# CM4_GPIO.net
KiCad netlist of a schematic drawn in Altium Designer
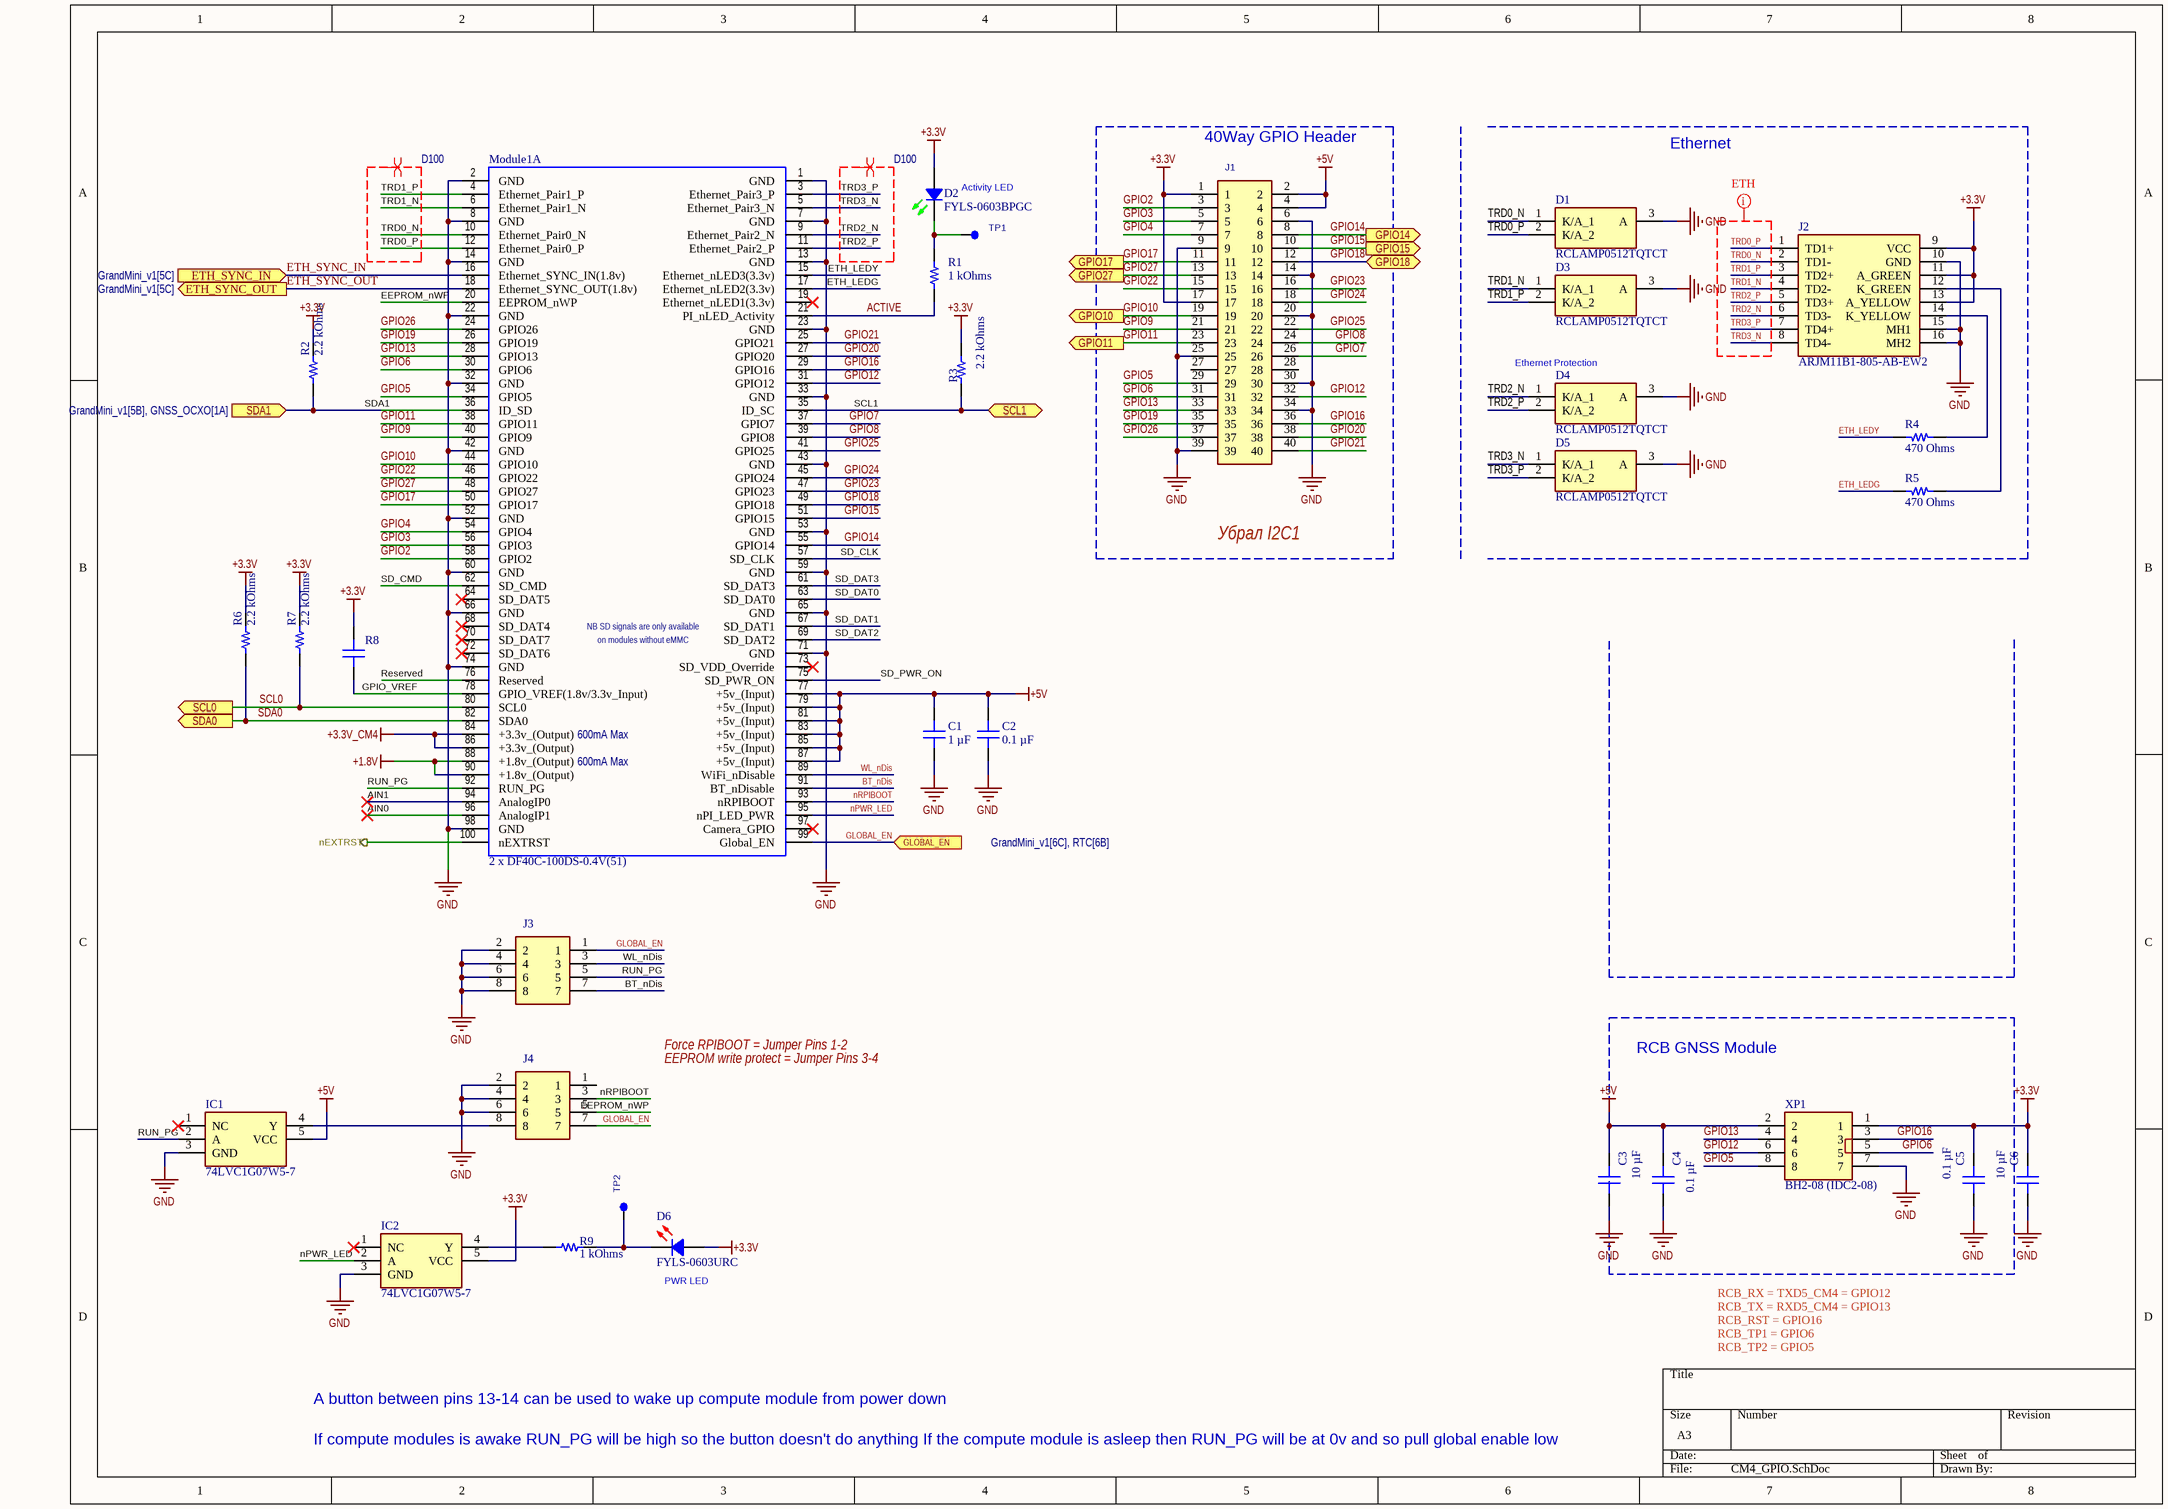
[diagram p0: CM4_GPIO.SchDoc]

(export (version "E")
  (design (tool "Eeschema 10.0.6"))
  (components
    (comp (ref "C1")
      (value "1 µF")
      (footprint "CAP 0603_1608")
      (description "CAP CER 1UF 50V X7R 0603")
      (fields (field (name "PART NUMBER") "CC0603KRX7R9BB105") (field (name "MANUFACTURER") "Yageo"))
      (libsource (lib "Celestial Altium Library - altium_library") (part "Capacitor"))
    )
    (comp (ref "C2")
      (value "0.1 µF")
      (footprint "CAP 0603_1608")
      (description "CAP CER 0.1UF 50V X7R 0603")
      (fields (field (name "PART NUMBER") "CC0603KRX7R9BB104") (field (name "MANUFACTURER") "Yageo"))
      (libsource (lib "Celestial Altium Library - altium_library") (part "Capacitor"))
    )
    (comp (ref "C3")
      (value "10 µF")
      (footprint "CAP 0805_2012")
      (description "CAP CER 10UF 25V X5R 0805")
      (fields (field (name "PART NUMBER") "CC0805KKX5R8BB106") (field (name "MANUFACTURER") "Yageo"))
      (libsource (lib "Celestial Altium Library - altium_library") (part "Capacitor"))
    )
    (comp (ref "C4")
      (value "0.1 µF")
      (footprint "CAP 0603_1608")
      (description "CAP CER 0.1UF 50V X7R 0603")
      (fields (field (name "PART NUMBER") "CC0603KRX7R9BB104") (field (name "MANUFACTURER") "Yageo"))
      (libsource (lib "Celestial Altium Library - altium_library") (part "Capacitor"))
    )
    (comp (ref "C5")
      (value "0.1 µF")
      (footprint "CAP 0603_1608")
      (description "CAP CER 0.1UF 50V X7R 0603")
      (fields (field (name "PART NUMBER") "CC0603KRX7R9BB104") (field (name "MANUFACTURER") "Yageo"))
      (libsource (lib "Celestial Altium Library - altium_library") (part "Capacitor"))
    )
    (comp (ref "C6")
      (value "10 µF")
      (footprint "CAP 0805_2012")
      (description "CAP CER 10UF 25V X5R 0805")
      (fields (field (name "PART NUMBER") "CC0805KKX5R8BB106") (field (name "MANUFACTURER") "Yageo"))
      (libsource (lib "Celestial Altium Library - altium_library") (part "Capacitor"))
    )
    (comp (ref "D1")
      (value "RCLAMP0512TQTCT")
      (footprint "RCLAMP0512TQTCT")
      (description "Diode")
      (fields (field (name "MOUSER PART NUMBER") "947-RCLAMP0512TQTCT"))
      (libsource (lib "SamacSys") (part "RCLAMP0512TQTCT"))
    )
    (comp (ref "D2")
      (value "FYLS-0603BPGC")
      (footprint "SamacSys:LEDC1608X55N_GREEN")
      (description "LED, 0603, GREEN")
      (libsource (lib "SamacSys") (part "FYLS-0603BPGC"))
    )
    (comp (ref "D3")
      (value "RCLAMP0512TQTCT")
      (footprint "RCLAMP0512TQTCT")
      (description "Diode")
      (fields (field (name "MOUSER PART NUMBER") "947-RCLAMP0512TQTCT"))
      (libsource (lib "SamacSys") (part "RCLAMP0512TQTCT"))
    )
    (comp (ref "D4")
      (value "RCLAMP0512TQTCT")
      (footprint "RCLAMP0512TQTCT")
      (description "Diode")
      (fields (field (name "MOUSER PART NUMBER") "947-RCLAMP0512TQTCT"))
      (libsource (lib "SamacSys") (part "RCLAMP0512TQTCT"))
    )
    (comp (ref "D5")
      (value "RCLAMP0512TQTCT")
      (footprint "RCLAMP0512TQTCT")
      (description "Diode")
      (fields (field (name "MOUSER PART NUMBER") "947-RCLAMP0512TQTCT"))
      (libsource (lib "SamacSys") (part "RCLAMP0512TQTCT"))
    )
    (comp (ref "D6")
      (value "FYLS-0603URC")
      (footprint "SamacSys:LEDC1608X55N_RED")
      (description "LED, 0603, RED")
      (libsource (lib "SamacSys") (part "FYLS-0603URC"))
    )
    (comp (ref "IC1")
      (value "74LVC1G07W5-7")
      (footprint "SamacSys:SOT95P285X140-5N")
      (description "Integrated Circuit")
      (fields (field (name "MOUSER PART NUMBER") "621-74LVC1G07W5-7"))
      (libsource (lib "*") (part "74LVC1G07W5-7"))
    )
    (comp (ref "IC2")
      (value "74LVC1G07W5-7")
      (footprint "SamacSys:SOT95P285X140-5N")
      (description "Integrated Circuit")
      (fields (field (name "MOUSER PART NUMBER") "621-74LVC1G07W5-7"))
      (libsource (lib "*") (part "74LVC1G07W5-7"))
    )
    (comp (ref "J1")
      (value "PBD-40")
      (footprint "SamacSys:PBD-40")
      (description "Connector")
      (fields (field (name "MANUFACTURER") "Connfly"))
      (libsource (lib "SamacSys") (part "PBD-40"))
    )
    (comp (ref "J2")
      (value "ARJM11B1-805-AB-EW2")
      (footprint "SamacSys:ARJM11B1805ABEW2")
      (description "Connector")
      (fields (field (name "MOUSER PART NUMBER") "815-RJM11B1805ABEW2"))
      (libsource (lib "SamacSys") (part "ARJM11B1-805-AB-EW2"))
    )
    (comp (ref "J3")
      (value "PLD-8")
      (footprint "PLD-8")
      (description "Connector")
      (fields (field (name "MANUFACTURER_PART_NUMBER") "S4B-PH-SM4-TB(LF)(SN)"))
      (libsource (lib "SamacSys") (part "PLD-8_1"))
    )
    (comp (ref "J4")
      (value "PLD-8")
      (footprint "PLD-8")
      (description "Connector")
      (fields (field (name "MANUFACTURER_PART_NUMBER") "S4B-PH-SM4-TB(LF)(SN)"))
      (libsource (lib "SamacSys") (part "PLD-8_1"))
    )
    (comp (ref "Module1")
      (value "2 x DF40C-100DS-0.4V(51)")
      (footprint "RPI_CM4_STACKED")
      (description "Rapsberry PI Compute Module 4 +")
      (libsource (lib "SamacSys") (part "RPi_CM4_1"))
    )
    (comp (ref "R1")
      (value "1 kOhms")
      (footprint "YAGEO RES 0603_1608")
      (description "RES 1K OHM 1% 1/10W 0603")
      (fields (field (name "PART NUMBER") "RC0603FR-071KL") (field (name "MANUFACTURER") "Yageo"))
      (libsource (lib "Celestial Altium Library - altium_library") (part "Resistor"))
    )
    (comp (ref "R2")
      (value "2.2 kOhms")
      (footprint "YAGEO RES 0402_1005")
      (description "RES 2.2K OHM 1% 1/16W 0402")
      (fields (field (name "PART NUMBER") "RC0402FR-072K2L") (field (name "MANUFACTURER") "Yageo"))
      (libsource (lib "Celestial Altium Library - altium_library") (part "Resistor"))
    )
    (comp (ref "R3")
      (value "2.2 kOhms")
      (footprint "YAGEO RES 0402_1005")
      (description "RES 2.2K OHM 1% 1/16W 0402")
      (fields (field (name "PART NUMBER") "RC0402FR-072K2L") (field (name "MANUFACTURER") "Yageo"))
      (libsource (lib "Celestial Altium Library - altium_library") (part "Resistor"))
    )
    (comp (ref "R4")
      (value "470 Ohms")
      (footprint "YAGEO RES 0402_1005")
      (description "RES 470 OHM 1% 1/16W 0402")
      (fields (field (name "TOLERANCE") "±1%") (field (name "MANUFACTURER") "Yageo"))
      (libsource (lib "Celestial Altium Library - altium_library") (part "Resistor"))
    )
    (comp (ref "R5")
      (value "470 Ohms")
      (footprint "YAGEO RES 0402_1005")
      (description "RES 470 OHM 1% 1/16W 0402")
      (fields (field (name "TOLERANCE") "±1%") (field (name "MANUFACTURER") "Yageo"))
      (libsource (lib "Celestial Altium Library - altium_library") (part "Resistor"))
    )
    (comp (ref "R6")
      (value "2.2 kOhms")
      (footprint "YAGEO RES 0402_1005")
      (description "RES 2.2K OHM 1% 1/16W 0402")
      (fields (field (name "PART NUMBER") "RC0402FR-072K2L") (field (name "MANUFACTURER") "Yageo"))
      (libsource (lib "Celestial Altium Library - altium_library") (part "Resistor"))
    )
    (comp (ref "R7")
      (value "2.2 kOhms")
      (footprint "YAGEO RES 0402_1005")
      (description "RES 2.2K OHM 1% 1/16W 0402")
      (fields (field (name "PART NUMBER") "RC0402FR-072K2L") (field (name "MANUFACTURER") "Yageo"))
      (libsource (lib "Celestial Altium Library - altium_library") (part "Resistor"))
    )
    (comp (ref "R8")
      (value "10 µF")
      (footprint "CAP 0805_2012")
      (description "CAP CER 10UF 25V X5R 0805")
      (fields (field (name "PART NUMBER") "CC0805KKX5R8BB106") (field (name "MANUFACTURER") "Yageo"))
      (libsource (lib "Celestial Altium Library - altium_library") (part "Capacitor"))
    )
    (comp (ref "R9")
      (value "1 kOhms")
      (footprint "YAGEO RES 0603_1608")
      (description "RES 1K OHM 1% 1/10W 0603")
      (fields (field (name "PART NUMBER") "RC0603FR-071KL") (field (name "MANUFACTURER") "Yageo"))
      (libsource (lib "Celestial Altium Library - altium_library") (part "Resistor"))
    )
    (comp (ref "TP1")
      (value "PAD_TEST")
      (footprint "Samacsys:PAD_TEST")
      (description "Test Point")
      (fields (field (name "TOLERANCE") "{Tolerance}") (field (name "MANUFACTURER") "{Manufacturer}"))
      (libsource (lib "SamacSys") (part "PAD_TEST"))
    )
    (comp (ref "TP2")
      (value "PAD_TEST")
      (footprint "Samacsys:PAD_TEST")
      (description "Test Point")
      (fields (field (name "TOLERANCE") "{Tolerance}") (field (name "MANUFACTURER") "{Manufacturer}"))
      (libsource (lib "SamacSys") (part "PAD_TEST"))
    )
    (comp (ref "XP1")
      (value "BH2-08 (IDC2-08)")
      (footprint "BH2-08")
      (description "Connector")
      (fields (field (name "MANUFACTURER_PART_NUMBER") "DS1014-08"))
      (libsource (lib "SamacSys") (part "BH2-08"))
    )
  )
  (nets
    (net (code "1") (name "+1.8V") (class "Default")
      (node (ref "Module1") (pin "88") (pinfunction "+1.8v_(Output)_88") (pintype "passive"))
      (node (ref "Module1") (pin "90") (pinfunction "+1.8v_(Output)_90") (pintype "passive"))
    )
    (net (code "2") (name "+3.3V") (class "Default")
      (node (ref "C5") (pin "2") (pinfunction "2_2") (pintype "passive"))
      (node (ref "C6") (pin "2") (pinfunction "2_2") (pintype "passive"))
      (node (ref "D2") (pin "2") (pinfunction "C_2") (pintype "passive"))
      (node (ref "D6") (pin "2") (pinfunction "C_2") (pintype "passive"))
      (node (ref "IC2") (pin "5") (pinfunction "VCC_5") (pintype "passive"))
      (node (ref "J1") (pin "1") (pinfunction "1_1") (pintype "passive"))
      (node (ref "J1") (pin "17") (pinfunction "17_17") (pintype "passive"))
      (node (ref "J2") (pin "11") (pinfunction "A_GREEN_11") (pintype "passive"))
      (node (ref "J2") (pin "13") (pinfunction "A_YELLOW_13") (pintype "passive"))
      (node (ref "J2") (pin "9") (pinfunction "VCC_9") (pintype "passive"))
      (node (ref "R2") (pin "2") (pinfunction "2_2") (pintype "passive"))
      (node (ref "R3") (pin "2") (pinfunction "2_2") (pintype "passive"))
      (node (ref "R6") (pin "2") (pinfunction "2_2") (pintype "passive"))
      (node (ref "R7") (pin "2") (pinfunction "2_2") (pintype "passive"))
      (node (ref "R8") (pin "2") (pinfunction "2_2") (pintype "passive"))
      (node (ref "XP1") (pin "1") (pinfunction "1_1") (pintype "passive"))
    )
    (net (code "3") (name "+3.3V_CM4") (class "Default")
      (node (ref "Module1") (pin "84") (pinfunction "+3.3v_(Output)_84") (pintype "passive"))
      (node (ref "Module1") (pin "86") (pinfunction "+3.3v_(Output)_86") (pintype "passive"))
    )
    (net (code "4") (name "+5V") (class "Default")
      (node (ref "C1") (pin "2") (pinfunction "2_2") (pintype "passive"))
      (node (ref "C2") (pin "2") (pinfunction "2_2") (pintype "passive"))
      (node (ref "C3") (pin "2") (pinfunction "2_2") (pintype "passive"))
      (node (ref "C4") (pin "2") (pinfunction "2_2") (pintype "passive"))
      (node (ref "IC1") (pin "5") (pinfunction "VCC_5") (pintype "passive"))
      (node (ref "J1") (pin "2") (pinfunction "2_2") (pintype "passive"))
      (node (ref "J1") (pin "4") (pinfunction "4_4") (pintype "passive"))
      (node (ref "Module1") (pin "77") (pinfunction "+5v_(Input)_77") (pintype "passive"))
      (node (ref "Module1") (pin "79") (pinfunction "+5v_(Input)_79") (pintype "passive"))
      (node (ref "Module1") (pin "81") (pinfunction "+5v_(Input)_81") (pintype "passive"))
      (node (ref "Module1") (pin "83") (pinfunction "+5v_(Input)_83") (pintype "passive"))
      (node (ref "Module1") (pin "85") (pinfunction "+5v_(Input)_85") (pintype "passive"))
      (node (ref "Module1") (pin "87") (pinfunction "+5v_(Input)_87") (pintype "passive"))
      (node (ref "XP1") (pin "2") (pinfunction "2_2") (pintype "passive"))
    )
    (net (code "5") (name "/ACTIVE") (class "Default")
      (node (ref "Module1") (pin "21") (pinfunction "PI_nLED_Activity_21") (pintype "passive"))
      (node (ref "R1") (pin "1") (pinfunction "1_1") (pintype "passive"))
    )
    (net (code "6") (name "/AIN0") (class "Default")
      (node (ref "Module1") (pin "96") (pinfunction "AnalogIP1_96") (pintype "passive+no_connect"))
    )
    (net (code "7") (name "/AIN1") (class "Default")
      (node (ref "Module1") (pin "94") (pinfunction "AnalogIP0_94") (pintype "passive+no_connect"))
    )
    (net (code "8") (name "/BT_nDis") (class "Default")
      (node (ref "J3") (pin "7") (pinfunction "7_7") (pintype "passive"))
      (node (ref "Module1") (pin "91") (pinfunction "BT_nDisable_91") (pintype "passive"))
    )
    (net (code "9") (name "/EEPROM_nWP") (class "Default")
      (node (ref "J4") (pin "5") (pinfunction "5_5") (pintype "passive"))
      (node (ref "Module1") (pin "20") (pinfunction "EEPROM_nWP_20") (pintype "passive"))
    )
    (net (code "10") (name "/ETH_LEDG") (class "Default")
      (node (ref "Module1") (pin "17") (pinfunction "Ethernet_nLED2(3.3v)_17") (pintype "passive"))
      (node (ref "R5") (pin "2") (pinfunction "2_2") (pintype "passive"))
    )
    (net (code "11") (name "/ETH_LEDY") (class "Default")
      (node (ref "Module1") (pin "15") (pinfunction "Ethernet_nLED3(3.3v)_15") (pintype "passive"))
      (node (ref "R4") (pin "2") (pinfunction "2_2") (pintype "passive"))
    )
    (net (code "12") (name "/ETH_SYNC_IN") (class "Default")
      (node (ref "Module1") (pin "16") (pinfunction "Ethernet_SYNC_IN(1.8v)_16") (pintype "passive"))
    )
    (net (code "13") (name "/ETH_SYNC_OUT") (class "Default")
      (node (ref "Module1") (pin "18") (pinfunction "Ethernet_SYNC_OUT(1.8v)_18") (pintype "passive"))
    )
    (net (code "14") (name "/GLOBAL_EN") (class "Default")
      (node (ref "J3") (pin "1") (pinfunction "1_1") (pintype "passive"))
      (node (ref "J4") (pin "7") (pinfunction "7_7") (pintype "passive"))
      (node (ref "Module1") (pin "99") (pinfunction "Global_EN_99") (pintype "passive"))
    )
    (net (code "15") (name "/GPIO2") (class "Default")
      (node (ref "J1") (pin "3") (pinfunction "3_3") (pintype "passive"))
      (node (ref "Module1") (pin "58") (pinfunction "GPIO2_58") (pintype "passive"))
    )
    (net (code "16") (name "/GPIO3") (class "Default")
      (node (ref "J1") (pin "5") (pinfunction "5_5") (pintype "passive"))
      (node (ref "Module1") (pin "56") (pinfunction "GPIO3_56") (pintype "passive"))
    )
    (net (code "17") (name "/GPIO4") (class "Default")
      (node (ref "J1") (pin "7") (pinfunction "7_7") (pintype "passive"))
      (node (ref "Module1") (pin "54") (pinfunction "GPIO4_54") (pintype "passive"))
    )
    (net (code "18") (name "/GPIO5") (class "Default")
      (node (ref "J1") (pin "29") (pinfunction "29_29") (pintype "passive"))
      (node (ref "Module1") (pin "34") (pinfunction "GPIO5_34") (pintype "passive"))
      (node (ref "XP1") (pin "8") (pinfunction "8_8") (pintype "passive"))
    )
    (net (code "19") (name "/GPIO6") (class "Default")
      (node (ref "J1") (pin "31") (pinfunction "31_31") (pintype "passive"))
      (node (ref "Module1") (pin "30") (pinfunction "GPIO6_30") (pintype "passive"))
      (node (ref "XP1") (pin "5") (pinfunction "5_5") (pintype "passive"))
    )
    (net (code "20") (name "/GPIO7") (class "Default")
      (node (ref "J1") (pin "26") (pinfunction "26_26") (pintype "passive"))
      (node (ref "Module1") (pin "37") (pinfunction "GPIO7_37") (pintype "passive"))
    )
    (net (code "21") (name "/GPIO8") (class "Default")
      (node (ref "J1") (pin "24") (pinfunction "24_24") (pintype "passive"))
      (node (ref "Module1") (pin "39") (pinfunction "GPIO8_39") (pintype "passive"))
    )
    (net (code "22") (name "/GPIO9") (class "Default")
      (node (ref "J1") (pin "21") (pinfunction "21_21") (pintype "passive"))
      (node (ref "Module1") (pin "40") (pinfunction "GPIO9_40") (pintype "passive"))
    )
    (net (code "23") (name "/GPIO10") (class "Default")
      (node (ref "J1") (pin "19") (pinfunction "19_19") (pintype "passive"))
      (node (ref "Module1") (pin "44") (pinfunction "GPIO10_44") (pintype "passive"))
    )
    (net (code "24") (name "/GPIO11") (class "Default")
      (node (ref "J1") (pin "23") (pinfunction "23_23") (pintype "passive"))
      (node (ref "Module1") (pin "38") (pinfunction "GPIO11_38") (pintype "passive"))
    )
    (net (code "25") (name "/GPIO12") (class "Default")
      (node (ref "J1") (pin "32") (pinfunction "32_32") (pintype "passive"))
      (node (ref "Module1") (pin "31") (pinfunction "GPIO12_31") (pintype "passive"))
      (node (ref "XP1") (pin "6") (pinfunction "6_6") (pintype "passive"))
    )
    (net (code "26") (name "/GPIO13") (class "Default")
      (node (ref "J1") (pin "33") (pinfunction "33_33") (pintype "passive"))
      (node (ref "Module1") (pin "28") (pinfunction "GPIO13_28") (pintype "passive"))
      (node (ref "XP1") (pin "4") (pinfunction "4_4") (pintype "passive"))
    )
    (net (code "27") (name "/GPIO14") (class "Default")
      (node (ref "J1") (pin "8") (pinfunction "8_8") (pintype "passive"))
      (node (ref "Module1") (pin "55") (pinfunction "GPIO14_55") (pintype "passive"))
    )
    (net (code "28") (name "/GPIO15") (class "Default")
      (node (ref "J1") (pin "10") (pinfunction "10_10") (pintype "passive"))
      (node (ref "Module1") (pin "51") (pinfunction "GPIO15_51") (pintype "passive"))
    )
    (net (code "29") (name "/GPIO16") (class "Default")
      (node (ref "J1") (pin "36") (pinfunction "36_36") (pintype "passive"))
      (node (ref "Module1") (pin "29") (pinfunction "GPIO16_29") (pintype "passive"))
      (node (ref "XP1") (pin "3") (pinfunction "3_3") (pintype "passive"))
    )
    (net (code "30") (name "/GPIO17") (class "Default")
      (node (ref "J1") (pin "11") (pinfunction "11_11") (pintype "passive"))
      (node (ref "Module1") (pin "50") (pinfunction "GPIO17_50") (pintype "passive"))
    )
    (net (code "31") (name "/GPIO18") (class "Default")
      (node (ref "J1") (pin "12") (pinfunction "12_12") (pintype "passive"))
      (node (ref "Module1") (pin "49") (pinfunction "GPIO18_49") (pintype "passive"))
    )
    (net (code "32") (name "/GPIO19") (class "Default")
      (node (ref "J1") (pin "35") (pinfunction "35_35") (pintype "passive"))
      (node (ref "Module1") (pin "26") (pinfunction "GPIO19_26") (pintype "passive"))
    )
    (net (code "33") (name "/GPIO20") (class "Default")
      (node (ref "J1") (pin "38") (pinfunction "38_38") (pintype "passive"))
      (node (ref "Module1") (pin "27") (pinfunction "GPIO20_27") (pintype "passive"))
    )
    (net (code "34") (name "/GPIO21") (class "Default")
      (node (ref "J1") (pin "40") (pinfunction "40_40") (pintype "passive"))
      (node (ref "Module1") (pin "25") (pinfunction "GPIO21_25") (pintype "passive"))
    )
    (net (code "35") (name "/GPIO22") (class "Default")
      (node (ref "J1") (pin "15") (pinfunction "15_15") (pintype "passive"))
      (node (ref "Module1") (pin "46") (pinfunction "GPIO22_46") (pintype "passive"))
    )
    (net (code "36") (name "/GPIO23") (class "Default")
      (node (ref "J1") (pin "16") (pinfunction "16_16") (pintype "passive"))
      (node (ref "Module1") (pin "47") (pinfunction "GPIO23_47") (pintype "passive"))
    )
    (net (code "37") (name "/GPIO24") (class "Default")
      (node (ref "J1") (pin "18") (pinfunction "18_18") (pintype "passive"))
      (node (ref "Module1") (pin "45") (pinfunction "GPIO24_45") (pintype "passive"))
    )
    (net (code "38") (name "/GPIO25") (class "Default")
      (node (ref "J1") (pin "22") (pinfunction "22_22") (pintype "passive"))
      (node (ref "Module1") (pin "41") (pinfunction "GPIO25_41") (pintype "passive"))
    )
    (net (code "39") (name "/GPIO26") (class "Default")
      (node (ref "J1") (pin "37") (pinfunction "37_37") (pintype "passive"))
      (node (ref "Module1") (pin "24") (pinfunction "GPIO26_24") (pintype "passive"))
    )
    (net (code "40") (name "/GPIO27") (class "Default")
      (node (ref "J1") (pin "13") (pinfunction "13_13") (pintype "passive"))
      (node (ref "Module1") (pin "48") (pinfunction "GPIO27_48") (pintype "passive"))
    )
    (net (code "41") (name "/GPIO_VREF") (class "Default")
      (node (ref "Module1") (pin "78") (pinfunction "GPIO_VREF(1.8v/3.3v_Input)_78") (pintype "passive"))
      (node (ref "R8") (pin "1") (pinfunction "1_1") (pintype "passive"))
    )
    (net (code "42") (name "/RUN_PG") (class "Default")
      (node (ref "IC1") (pin "2") (pinfunction "A_2") (pintype "passive"))
      (node (ref "J3") (pin "5") (pinfunction "5_5") (pintype "passive"))
      (node (ref "Module1") (pin "92") (pinfunction "RUN_PG_92") (pintype "passive"))
    )
    (net (code "44") (name "/SCL0") (class "Default")
      (node (ref "Module1") (pin "80") (pinfunction "SCL0_80") (pintype "passive"))
      (node (ref "R7") (pin "1") (pinfunction "1_1") (pintype "passive"))
    )
    (net (code "45") (name "/SCL1") (class "Default")
      (node (ref "Module1") (pin "35") (pinfunction "ID_SC_35") (pintype "passive"))
      (node (ref "R3") (pin "1") (pinfunction "1_1") (pintype "passive"))
    )
    (net (code "46") (name "/SDA0") (class "Default")
      (node (ref "Module1") (pin "82") (pinfunction "SDA0_82") (pintype "passive"))
      (node (ref "R6") (pin "1") (pinfunction "1_1") (pintype "passive"))
    )
    (net (code "47") (name "/SDA1") (class "Default")
      (node (ref "Module1") (pin "36") (pinfunction "ID_SD_36") (pintype "passive"))
      (node (ref "R2") (pin "1") (pinfunction "1_1") (pintype "passive"))
    )
    (net (code "48") (name "/SD_CLK") (class "Default")
      (node (ref "Module1") (pin "57") (pinfunction "SD_CLK_57") (pintype "passive"))
    )
    (net (code "49") (name "/SD_CMD") (class "Default")
      (node (ref "Module1") (pin "62") (pinfunction "SD_CMD_62") (pintype "passive"))
    )
    (net (code "50") (name "/SD_DAT0") (class "Default")
      (node (ref "Module1") (pin "63") (pinfunction "SD_DAT0_63") (pintype "passive"))
    )
    (net (code "51") (name "/SD_DAT1") (class "Default")
      (node (ref "Module1") (pin "67") (pinfunction "SD_DAT1_67") (pintype "passive"))
    )
    (net (code "52") (name "/SD_DAT2") (class "Default")
      (node (ref "Module1") (pin "69") (pinfunction "SD_DAT2_69") (pintype "passive"))
    )
    (net (code "53") (name "/SD_DAT3") (class "Default")
      (node (ref "Module1") (pin "61") (pinfunction "SD_DAT3_61") (pintype "passive"))
    )
    (net (code "54") (name "/SD_PWR_ON") (class "Default")
      (node (ref "Module1") (pin "75") (pinfunction "SD_PWR_ON_75") (pintype "passive"))
    )
    (net (code "55") (name "/TRD0_N") (class "Default")
      (node (ref "D1") (pin "1") (pinfunction "K/A_1_1") (pintype "passive"))
      (node (ref "J2") (pin "2") (pinfunction "TD1-_2") (pintype "passive"))
      (node (ref "Module1") (pin "10") (pinfunction "Ethernet_Pair0_N_10") (pintype "passive"))
    )
    (net (code "56") (name "/TRD0_P") (class "Default")
      (node (ref "D1") (pin "2") (pinfunction "K/A_2_2") (pintype "passive"))
      (node (ref "J2") (pin "1") (pinfunction "TD1+_1") (pintype "passive"))
      (node (ref "Module1") (pin "12") (pinfunction "Ethernet_Pair0_P_12") (pintype "passive"))
    )
    (net (code "57") (name "/TRD1_N") (class "Default")
      (node (ref "D3") (pin "1") (pinfunction "K/A_1_1") (pintype "passive"))
      (node (ref "J2") (pin "4") (pinfunction "TD2-_4") (pintype "passive"))
      (node (ref "Module1") (pin "6") (pinfunction "Ethernet_Pair1_N_6") (pintype "passive"))
    )
    (net (code "58") (name "/TRD1_P") (class "Default")
      (node (ref "D3") (pin "2") (pinfunction "K/A_2_2") (pintype "passive"))
      (node (ref "J2") (pin "3") (pinfunction "TD2+_3") (pintype "passive"))
      (node (ref "Module1") (pin "4") (pinfunction "Ethernet_Pair1_P_4") (pintype "passive"))
    )
    (net (code "59") (name "/TRD2_N") (class "Default")
      (node (ref "D4") (pin "1") (pinfunction "K/A_1_1") (pintype "passive"))
      (node (ref "J2") (pin "6") (pinfunction "TD3-_6") (pintype "passive"))
      (node (ref "Module1") (pin "9") (pinfunction "Ethernet_Pair2_N_9") (pintype "passive"))
    )
    (net (code "60") (name "/TRD2_P") (class "Default")
      (node (ref "D4") (pin "2") (pinfunction "K/A_2_2") (pintype "passive"))
      (node (ref "J2") (pin "5") (pinfunction "TD3+_5") (pintype "passive"))
      (node (ref "Module1") (pin "11") (pinfunction "Ethernet_Pair2_P_11") (pintype "passive"))
    )
    (net (code "61") (name "/TRD3_N") (class "Default")
      (node (ref "D5") (pin "1") (pinfunction "K/A_1_1") (pintype "passive"))
      (node (ref "J2") (pin "8") (pinfunction "TD4-_8") (pintype "passive"))
      (node (ref "Module1") (pin "5") (pinfunction "Ethernet_Pair3_N_5") (pintype "passive"))
    )
    (net (code "62") (name "/TRD3_P") (class "Default")
      (node (ref "D5") (pin "2") (pinfunction "K/A_2_2") (pintype "passive"))
      (node (ref "J2") (pin "7") (pinfunction "TD4+_7") (pintype "passive"))
      (node (ref "Module1") (pin "3") (pinfunction "Ethernet_Pair3_P_3") (pintype "passive"))
    )
    (net (code "63") (name "/WL_nDis") (class "Default")
      (node (ref "J3") (pin "3") (pinfunction "3_3") (pintype "passive"))
      (node (ref "Module1") (pin "89") (pinfunction "WiFi_nDisable_89") (pintype "passive"))
    )
    (net (code "64") (name "/nEXTRST") (class "Default")
      (node (ref "Module1") (pin "100") (pinfunction "nEXTRST_100") (pintype "passive"))
    )
    (net (code "65") (name "/nPWR_LED") (class "Default")
      (node (ref "IC2") (pin "2") (pinfunction "A_2") (pintype "passive"))
      (node (ref "Module1") (pin "95") (pinfunction "nPI_LED_PWR_95") (pintype "passive"))
    )
    (net (code "66") (name "/nRPIBOOT") (class "Default")
      (node (ref "J4") (pin "3") (pinfunction "3_3") (pintype "passive"))
      (node (ref "Module1") (pin "93") (pinfunction "nRPIBOOT_93") (pintype "passive"))
    )
    (net (code "67") (name "GND") (class "Default")
      (node (ref "C1") (pin "1") (pinfunction "1_1") (pintype "passive"))
      (node (ref "C2") (pin "1") (pinfunction "1_1") (pintype "passive"))
      (node (ref "C3") (pin "1") (pinfunction "1_1") (pintype "passive"))
      (node (ref "C4") (pin "1") (pinfunction "1_1") (pintype "passive"))
      (node (ref "C5") (pin "1") (pinfunction "1_1") (pintype "passive"))
      (node (ref "C6") (pin "1") (pinfunction "1_1") (pintype "passive"))
      (node (ref "D1") (pin "3") (pinfunction "A_3") (pintype "passive"))
      (node (ref "D3") (pin "3") (pinfunction "A_3") (pintype "passive"))
      (node (ref "D4") (pin "3") (pinfunction "A_3") (pintype "passive"))
      (node (ref "D5") (pin "3") (pinfunction "A_3") (pintype "passive"))
      (node (ref "IC1") (pin "3") (pinfunction "GND_3") (pintype "passive"))
      (node (ref "IC2") (pin "3") (pinfunction "GND_3") (pintype "passive"))
      (node (ref "J1") (pin "14") (pinfunction "14_14") (pintype "passive"))
      (node (ref "J1") (pin "20") (pinfunction "20_20") (pintype "passive"))
      (node (ref "J1") (pin "25") (pinfunction "25_25") (pintype "passive"))
      (node (ref "J1") (pin "30") (pinfunction "30_30") (pintype "passive"))
      (node (ref "J1") (pin "34") (pinfunction "34_34") (pintype "passive"))
      (node (ref "J1") (pin "39") (pinfunction "39_39") (pintype "passive"))
      (node (ref "J1") (pin "6") (pinfunction "6_6") (pintype "passive"))
      (node (ref "J1") (pin "9") (pinfunction "9_9") (pintype "passive"))
      (node (ref "J2") (pin "10") (pinfunction "GND_10") (pintype "passive"))
      (node (ref "J2") (pin "15") (pinfunction "MH1_15") (pintype "passive"))
      (node (ref "J2") (pin "16") (pinfunction "MH2_16") (pintype "passive"))
      (node (ref "J3") (pin "2") (pinfunction "2_2") (pintype "passive"))
      (node (ref "J3") (pin "4") (pinfunction "4_4") (pintype "passive"))
      (node (ref "J3") (pin "6") (pinfunction "6_6") (pintype "passive"))
      (node (ref "J3") (pin "8") (pinfunction "8_8") (pintype "passive"))
      (node (ref "J4") (pin "2") (pinfunction "2_2") (pintype "passive"))
      (node (ref "J4") (pin "4") (pinfunction "4_4") (pintype "passive"))
      (node (ref "J4") (pin "6") (pinfunction "6_6") (pintype "passive"))
      (node (ref "Module1") (pin "1") (pinfunction "GND_1") (pintype "passive"))
      (node (ref "Module1") (pin "13") (pinfunction "GND_13") (pintype "passive"))
      (node (ref "Module1") (pin "14") (pinfunction "GND_14") (pintype "passive"))
      (node (ref "Module1") (pin "2") (pinfunction "GND_2") (pintype "passive"))
      (node (ref "Module1") (pin "22") (pinfunction "GND_22") (pintype "passive"))
      (node (ref "Module1") (pin "23") (pinfunction "GND_23") (pintype "passive"))
      (node (ref "Module1") (pin "32") (pinfunction "GND_32") (pintype "passive"))
      (node (ref "Module1") (pin "33") (pinfunction "GND_33") (pintype "passive"))
      (node (ref "Module1") (pin "42") (pinfunction "GND_42") (pintype "passive"))
      (node (ref "Module1") (pin "43") (pinfunction "GND_43") (pintype "passive"))
      (node (ref "Module1") (pin "52") (pinfunction "GND_52") (pintype "passive"))
      (node (ref "Module1") (pin "53") (pinfunction "GND_53") (pintype "passive"))
      (node (ref "Module1") (pin "59") (pinfunction "GND_59") (pintype "passive"))
      (node (ref "Module1") (pin "60") (pinfunction "GND_60") (pintype "passive"))
      (node (ref "Module1") (pin "65") (pinfunction "GND_65") (pintype "passive"))
      (node (ref "Module1") (pin "66") (pinfunction "GND_66") (pintype "passive"))
      (node (ref "Module1") (pin "7") (pinfunction "GND_7") (pintype "passive"))
      (node (ref "Module1") (pin "71") (pinfunction "GND_71") (pintype "passive"))
      (node (ref "Module1") (pin "74") (pinfunction "GND_74") (pintype "passive"))
      (node (ref "Module1") (pin "8") (pinfunction "GND_8") (pintype "passive"))
      (node (ref "Module1") (pin "98") (pinfunction "GND_98") (pintype "passive"))
      (node (ref "XP1") (pin "7") (pinfunction "7_7") (pintype "passive"))
    )
    (net (code "68") (name "Net-(D2-A)") (class "Default")
      (node (ref "D2") (pin "1") (pinfunction "A_1") (pintype "passive"))
      (node (ref "R1") (pin "2") (pinfunction "2_2") (pintype "passive"))
      (node (ref "TP1") (pin "1") (pinfunction "1_1") (pintype "passive"))
    )
    (net (code "69") (name "Net-(D6-A)") (class "Default")
      (node (ref "D6") (pin "1") (pinfunction "A_1") (pintype "passive"))
      (node (ref "R9") (pin "2") (pinfunction "2_2") (pintype "passive"))
      (node (ref "TP2") (pin "1") (pinfunction "1_1") (pintype "passive"))
    )
    (net (code "70") (name "Net-(IC1-Y)") (class "Default")
      (node (ref "IC1") (pin "4") (pinfunction "Y_4") (pintype "passive"))
      (node (ref "J4") (pin "8") (pinfunction "8_8") (pintype "passive"))
    )
    (net (code "71") (name "Net-(IC2-Y)") (class "Default")
      (node (ref "IC2") (pin "4") (pinfunction "Y_4") (pintype "passive"))
      (node (ref "R9") (pin "1") (pinfunction "1_1") (pintype "passive"))
    )
    (net (code "72") (name "Net-(J2-K_GREEN)") (class "Default")
      (node (ref "J2") (pin "12") (pinfunction "K_GREEN_12") (pintype "passive"))
      (node (ref "R5") (pin "1") (pinfunction "1_1") (pintype "passive"))
    )
    (net (code "73") (name "Net-(J2-K_YELLOW)") (class "Default")
      (node (ref "J2") (pin "14") (pinfunction "K_YELLOW_14") (pintype "passive"))
      (node (ref "R4") (pin "1") (pinfunction "1_1") (pintype "passive"))
    )
    (net (code "74") (name "unconnected-(IC1-NC-Pad1)") (class "Default")
      (node (ref "IC1") (pin "1") (pinfunction "NC_1") (pintype "passive+no_connect"))
    )
    (net (code "75") (name "unconnected-(IC2-NC-Pad1)") (class "Default")
      (node (ref "IC2") (pin "1") (pinfunction "NC_1") (pintype "passive+no_connect"))
    )
    (net (code "76") (name "unconnected-(J1-Pad27)") (class "Default")
      (node (ref "J1") (pin "27") (pinfunction "27_27") (pintype "passive"))
    )
    (net (code "77") (name "unconnected-(J1-Pad28)") (class "Default")
      (node (ref "J1") (pin "28") (pinfunction "28_28") (pintype "passive"))
    )
    (net (code "78") (name "unconnected-(J4-Pad1)") (class "Default")
      (node (ref "J4") (pin "1") (pinfunction "1_1") (pintype "passive"))
    )
    (net (code "79") (name "unconnected-(Module1A-Camera_GPIO-Pad97)") (class "Default")
      (node (ref "Module1") (pin "97") (pinfunction "Camera_GPIO_97") (pintype "passive+no_connect"))
    )
    (net (code "80") (name "unconnected-(Module1A-Ethernet_nLED1(3.3v)-Pad19)") (class "Default")
      (node (ref "Module1") (pin "19") (pinfunction "Ethernet_nLED1(3.3v)_19") (pintype "passive+no_connect"))
    )
    (net (code "81") (name "unconnected-(Module1A-Reserved-Pad76)") (class "Default")
      (node (ref "Module1") (pin "76") (pinfunction "Reserved_76") (pintype "passive"))
    )
    (net (code "82") (name "unconnected-(Module1A-SD_DAT4-Pad68)") (class "Default")
      (node (ref "Module1") (pin "68") (pinfunction "SD_DAT4_68") (pintype "passive+no_connect"))
    )
    (net (code "83") (name "unconnected-(Module1A-SD_DAT5-Pad64)") (class "Default")
      (node (ref "Module1") (pin "64") (pinfunction "SD_DAT5_64") (pintype "passive+no_connect"))
    )
    (net (code "84") (name "unconnected-(Module1A-SD_DAT6-Pad72)") (class "Default")
      (node (ref "Module1") (pin "72") (pinfunction "SD_DAT6_72") (pintype "passive+no_connect"))
    )
    (net (code "85") (name "unconnected-(Module1A-SD_DAT7-Pad70)") (class "Default")
      (node (ref "Module1") (pin "70") (pinfunction "SD_DAT7_70") (pintype "passive+no_connect"))
    )
    (net (code "86") (name "unconnected-(Module1A-SD_VDD_Override-Pad73)") (class "Default")
      (node (ref "Module1") (pin "73") (pinfunction "SD_VDD_Override_73") (pintype "passive+no_connect"))
    )
  )
)
